# 0_Overview.net
KiCad netlist of a schematic drawn in Altium Designer
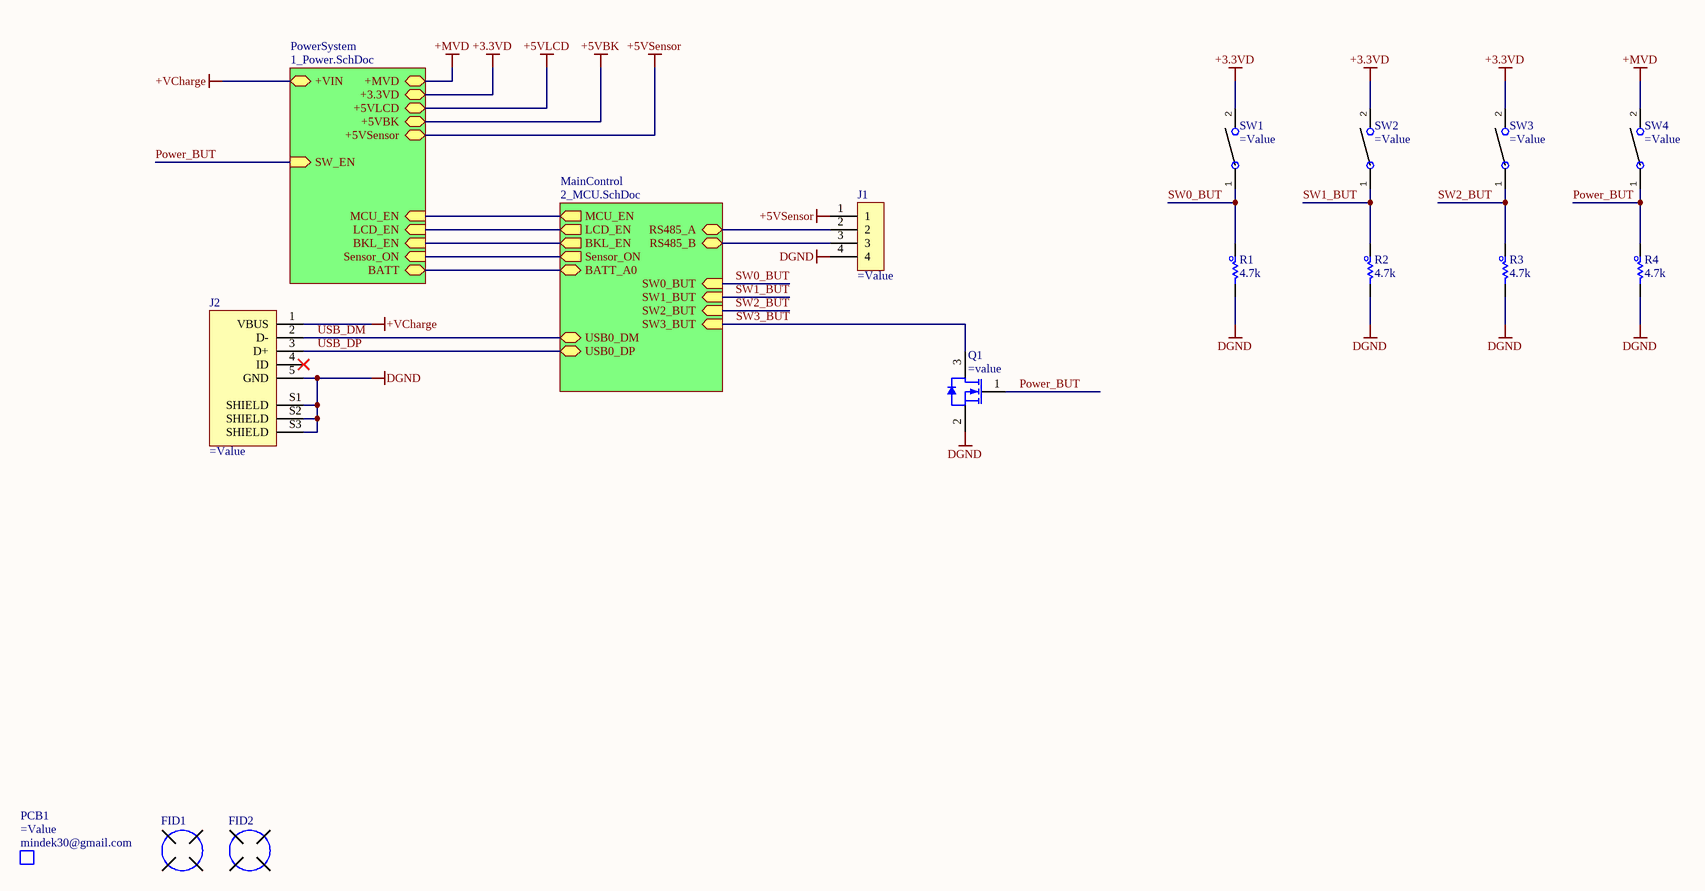
[diagram p0: 0_Overview.SchDoc]

(export (version "E")
  (design (tool "Eeschema 10.0.6"))
  (components
    (comp (ref "FID1")
      (value "FIDUCIAL")
      (footprint "FID")
      (description "Fiducial")
      (fields (field (name "MANUFACTURER") "mindek30@gmail.com") (field (name "PARTNUMBER") "_"))
      (libsource (lib "UUSymbol") (part "FID_FIDUCIAL"))
    )
    (comp (ref "FID2")
      (value "FIDUCIAL")
      (footprint "FID")
      (description "Fiducial")
      (fields (field (name "MANUFACTURER") "mindek30@gmail.com") (field (name "PARTNUMBER") "_"))
      (libsource (lib "UUSymbol") (part "FID_FIDUCIAL"))
    )
    (comp (ref "J1")
      (value "~")
      (footprint "CON_4P_Header")
      (description "Connector 4 position")
      (libsource (lib "UUSymbol") (part "CON_4P_Heder"))
    )
    (comp (ref "J2")
      (value "~")
      (footprint "MOLEX_105133-0011")
      (description "USB 2.0 1 Brick nogging 5 Female Micro-B SMD USB Connectors ROHS")
      (fields (field (name "PARTNUMBER") "1051330011") (field (name "MANUFACTURER") "Molex"))
      (libsource (lib "UUSymbol") (part "CON_USBMiniB_TH"))
    )
    (comp (ref "PCB1")
      (value "~")
      (description "BARE PCB")
      (fields (field (name "MANUFACTURER") "mindek30@gmail.com") (field (name "PARTNUMBER") "_"))
      (libsource (lib "UUSymbol") (part "PCB_Bare"))
    )
    (comp (ref "Q1")
      (value "~")
      (footprint "SOT95P245X110-3M")
      (description "MOSFET N-Channel 60V/250mA,0.2W")
      (fields (field (name "MANUFACTURER") "ROHM") (field (name "PARTNUMBER") "RK7002BMT116"))
      (libsource (lib "UUSymbol") (part "Q_NMOS_RK7002BMT116"))
    )
    (comp (ref "R1")
      (value "4.7k")
      (footprint "R_0603")
      (description "RES 4.7K OHM 5% 1/10W 0603")
      (fields (field (name "MANUFACTURER") "Vishay Dale") (field (name "PARTNUMBER") "CRCW06034K70JNEBC"))
      (libsource (lib "UUSymbol") (part "R_Resister"))
    )
    (comp (ref "R2")
      (value "4.7k")
      (footprint "R_0603")
      (description "RES 4.7K OHM 5% 1/10W 0603")
      (fields (field (name "MANUFACTURER") "Vishay Dale") (field (name "PARTNUMBER") "CRCW06034K70JNEBC"))
      (libsource (lib "UUSymbol") (part "R_Resister"))
    )
    (comp (ref "R3")
      (value "4.7k")
      (footprint "R_0603")
      (description "RES 4.7K OHM 5% 1/10W 0603")
      (fields (field (name "MANUFACTURER") "Vishay Dale") (field (name "PARTNUMBER") "CRCW06034K70JNEBC"))
      (libsource (lib "UUSymbol") (part "R_Resister"))
    )
    (comp (ref "R4")
      (value "4.7k")
      (footprint "R_0603")
      (description "RES 4.7K OHM 5% 1/10W 0603")
      (fields (field (name "MANUFACTURER") "Vishay Dale") (field (name "PARTNUMBER") "CRCW06034K70JNEBC"))
      (libsource (lib "UUSymbol") (part "R_Resister"))
    )
    (comp (ref "SW1")
      (value "~")
      (footprint "Tactile")
      (description "SWITCH TACTILE SPST-NO 0.05A 50V")
      (fields (field (name "PARTNUMBER") "TC-0308-X-ROHS") (field (name "MANUFACTURER") "WEALTH METAL"))
      (libsource (lib "UUSymbol") (part "SW_TAC_TH"))
    )
    (comp (ref "SW2")
      (value "~")
      (footprint "Tactile")
      (description "SWITCH TACTILE SPST-NO 0.05A 50V")
      (fields (field (name "PARTNUMBER") "TC-0308-X-ROHS") (field (name "MANUFACTURER") "WEALTH METAL"))
      (libsource (lib "UUSymbol") (part "SW_TAC_TH"))
    )
    (comp (ref "SW3")
      (value "~")
      (footprint "Tactile")
      (description "SWITCH TACTILE SPST-NO 0.05A 50V")
      (fields (field (name "PARTNUMBER") "TC-0308-X-ROHS") (field (name "MANUFACTURER") "WEALTH METAL"))
      (libsource (lib "UUSymbol") (part "SW_TAC_TH"))
    )
    (comp (ref "SW4")
      (value "~")
      (footprint "Tactile")
      (description "SWITCH TACTILE SPST-NO 0.05A 50V")
      (fields (field (name "PARTNUMBER") "TC-0308-X-ROHS") (field (name "MANUFACTURER") "WEALTH METAL"))
      (libsource (lib "UUSymbol") (part "SW_TAC_TH"))
    )
  )
  (nets
    (net (code "1") (name "+3.3VD") (class "Default")
      (node (ref "SW1") (pin "2") (pinfunction "2_2") (pintype "passive"))
      (node (ref "SW2") (pin "2") (pinfunction "2_2") (pintype "passive"))
      (node (ref "SW3") (pin "2") (pinfunction "2_2") (pintype "passive"))
    )
    (net (code "4") (name "+5VSensor") (class "Default")
      (node (ref "J1") (pin "1") (pinfunction "1_1") (pintype "passive"))
    )
    (net (code "5") (name "+MVD") (class "Default")
      (node (ref "SW4") (pin "2") (pinfunction "2_2") (pintype "passive"))
    )
    (net (code "6") (name "+VCharge") (class "Default")
      (node (ref "J2") (pin "1") (pinfunction "VBUS_1") (pintype "passive"))
    )
    (net (code "11") (name "/Power_BUT") (class "Default")
      (node (ref "Q1") (pin "1") (pinfunction "G_1") (pintype "passive"))
      (node (ref "R4") (pin "1") (pinfunction "1_1") (pintype "passive"))
      (node (ref "SW4") (pin "1") (pinfunction "1_1") (pintype "passive"))
    )
    (net (code "12") (name "/RS485_A") (class "Default")
      (node (ref "J1") (pin "2") (pinfunction "2_2") (pintype "passive"))
    )
    (net (code "13") (name "/RS485_B") (class "Default")
      (node (ref "J1") (pin "3") (pinfunction "3_3") (pintype "passive"))
    )
    (net (code "14") (name "/SW0_BUT") (class "Default")
      (node (ref "R1") (pin "1") (pinfunction "1_1") (pintype "passive"))
      (node (ref "SW1") (pin "1") (pinfunction "1_1") (pintype "passive"))
    )
    (net (code "15") (name "/SW1_BUT") (class "Default")
      (node (ref "R2") (pin "1") (pinfunction "1_1") (pintype "passive"))
      (node (ref "SW2") (pin "1") (pinfunction "1_1") (pintype "passive"))
    )
    (net (code "16") (name "/SW2_BUT") (class "Default")
      (node (ref "R3") (pin "1") (pinfunction "1_1") (pintype "passive"))
      (node (ref "SW3") (pin "1") (pinfunction "1_1") (pintype "passive"))
    )
    (net (code "17") (name "/SW3_BUT") (class "Default")
      (node (ref "Q1") (pin "3") (pinfunction "D_3") (pintype "passive"))
    )
    (net (code "19") (name "/USB_DM") (class "Default")
      (node (ref "J2") (pin "2") (pinfunction "D-_2") (pintype "passive"))
    )
    (net (code "20") (name "/USB_DP") (class "Default")
      (node (ref "J2") (pin "3") (pinfunction "D+_3") (pintype "passive"))
    )
    (net (code "21") (name "DGND") (class "Default")
      (node (ref "J1") (pin "4") (pinfunction "4_4") (pintype "passive"))
      (node (ref "J2") (pin "5") (pinfunction "GND_5") (pintype "passive"))
      (node (ref "J2") (pin "S1") (pinfunction "SHIELD_S1") (pintype "passive"))
      (node (ref "J2") (pin "S2") (pinfunction "SHIELD_S2") (pintype "passive"))
      (node (ref "J2") (pin "S3") (pinfunction "SHIELD_S3") (pintype "passive"))
      (node (ref "Q1") (pin "2") (pinfunction "S_2") (pintype "passive"))
      (node (ref "R1") (pin "2") (pinfunction "2_2") (pintype "passive"))
      (node (ref "R2") (pin "2") (pinfunction "2_2") (pintype "passive"))
      (node (ref "R3") (pin "2") (pinfunction "2_2") (pintype "passive"))
      (node (ref "R4") (pin "2") (pinfunction "2_2") (pintype "passive"))
    )
    (net (code "22") (name "unconnected-(J2-ID-Pad4)") (class "Default")
      (node (ref "J2") (pin "4") (pinfunction "ID_4") (pintype "passive+no_connect"))
    )
  )
)
